# Logic_Engine_v0_1.net
KiCad netlist of a schematic drawn in EAGLE
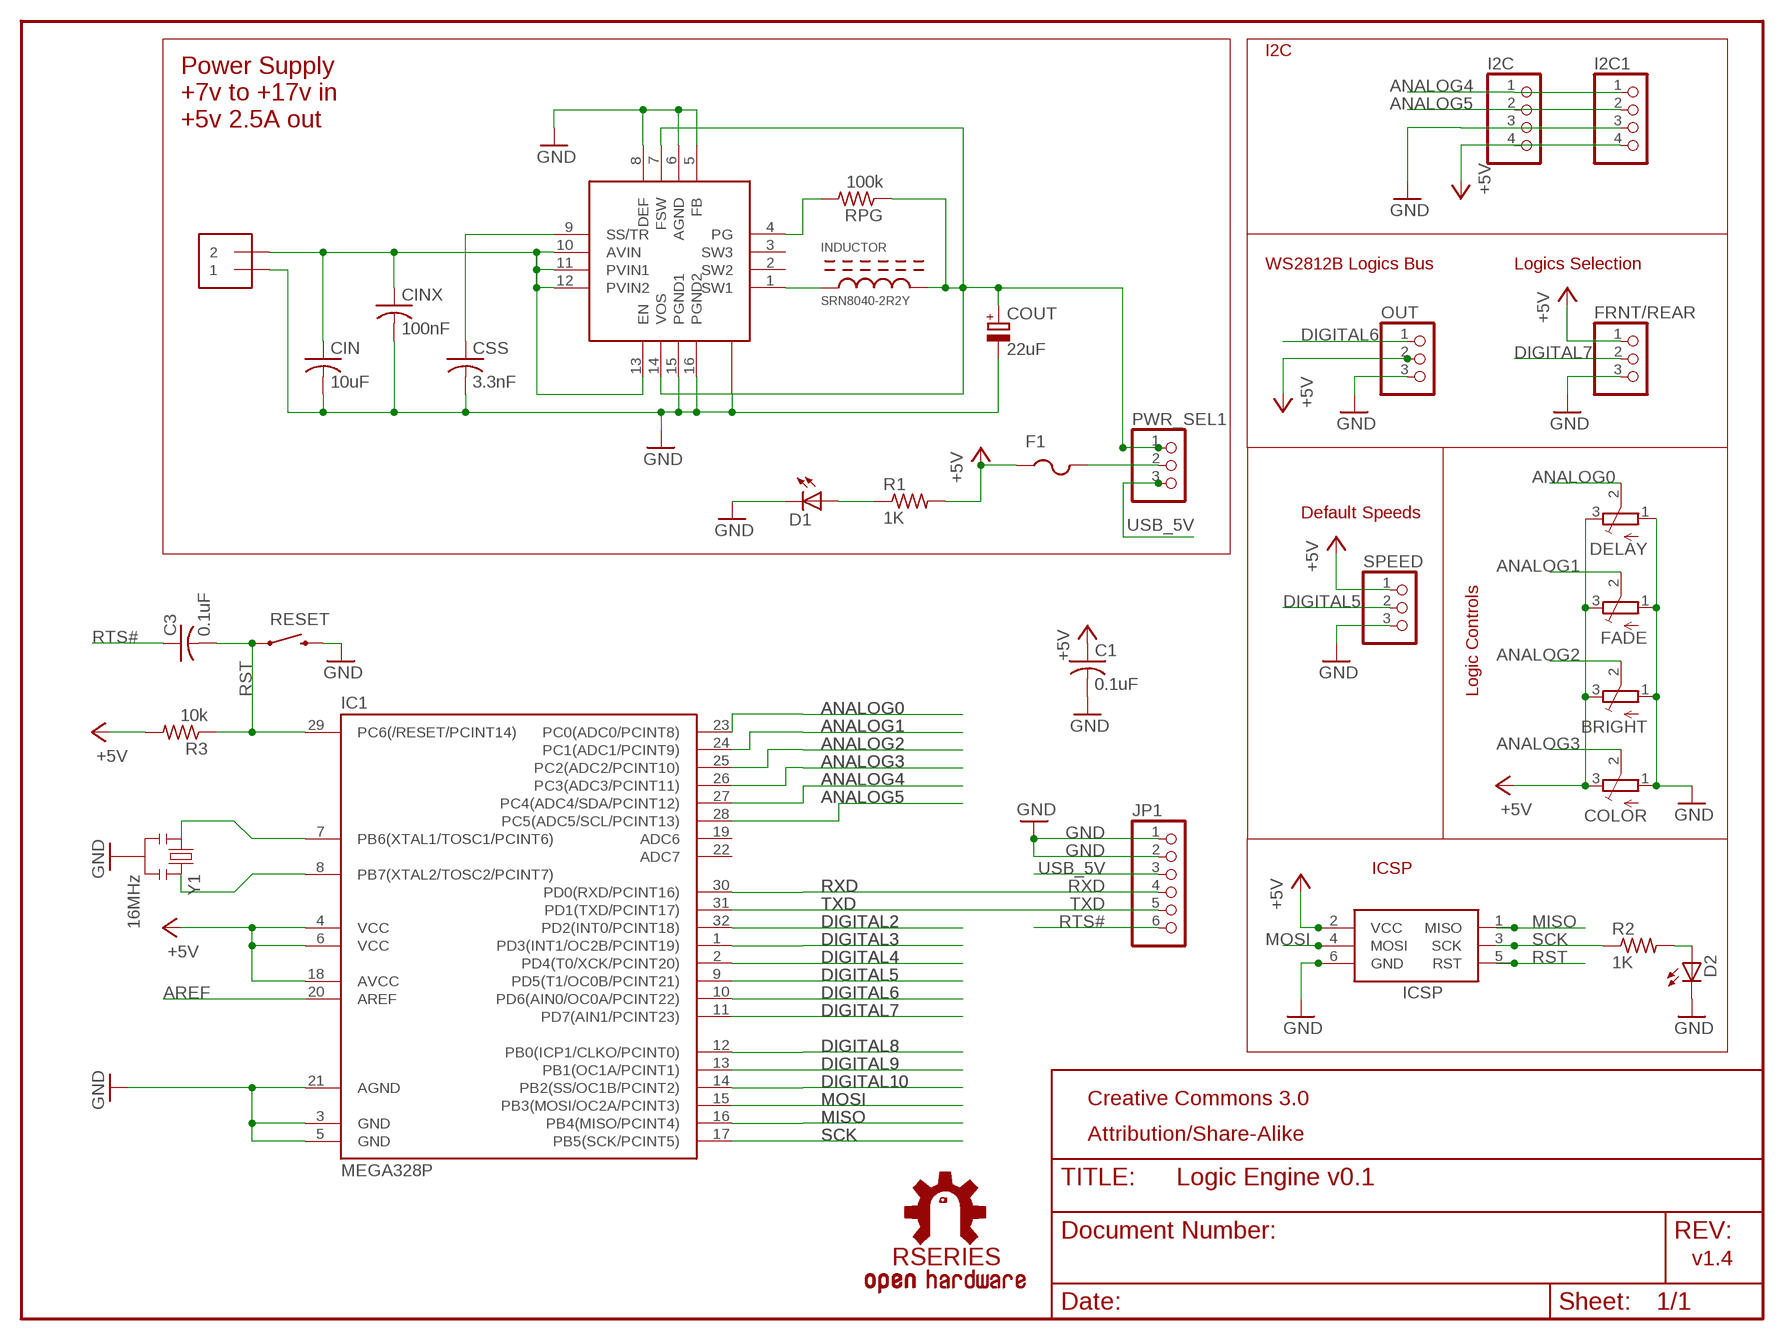
[diagram p0: schematic, sheet 1]

(export (version "E")
  (design (tool "Eeschema 10.0.6"))
  (components
    (comp (ref "BRIGHT")
      (value "TRIMPOT3364W")
      (footprint "eagle-import:3364")
      (libsource (lib "eagle-import") (part "TRIMPOT3364W"))
    )
    (comp (ref "C1")
      (value "0.1uF")
      (footprint "eagle-import:C0805K")
      (libsource (lib "eagle-import") (part "C-USC0805K"))
    )
    (comp (ref "C3")
      (value "0.1uF")
      (footprint "eagle-import:C0805K")
      (libsource (lib "eagle-import") (part "C-USC0805K"))
    )
    (comp (ref "CIN")
      (value "10uF")
      (footprint "eagle-import:C1206")
      (libsource (lib "eagle-import") (part "C-USC1206"))
    )
    (comp (ref "CINX")
      (value "100nF")
      (footprint "eagle-import:C0805K")
      (libsource (lib "eagle-import") (part "C-USC0805K"))
    )
    (comp (ref "COLOR")
      (value "TRIMPOT3364W")
      (footprint "eagle-import:3364")
      (libsource (lib "eagle-import") (part "TRIMPOT3364W"))
    )
    (comp (ref "COUT")
      (value "22uF")
      (footprint "eagle-import:CASE_B")
      (libsource (lib "eagle-import") (part "CAPACITOR_POL-CASE_B"))
    )
    (comp (ref "CSS")
      (value "3.3nF")
      (footprint "eagle-import:C0805K")
      (libsource (lib "eagle-import") (part "C-USC0805K"))
    )
    (comp (ref "D1")
      (value "LEDCHIPLED_1206")
      (footprint "eagle-import:CHIPLED_1206")
      (libsource (lib "eagle-import") (part "LEDCHIPLED_1206"))
    )
    (comp (ref "D2")
      (value "Green")
      (footprint "eagle-import:CHIPLED_1206")
      (libsource (lib "eagle-import") (part "LEDCHIPLED_1206"))
    )
    (comp (ref "DELAY")
      (value "TRIMPOT3364W")
      (footprint "eagle-import:3364")
      (libsource (lib "eagle-import") (part "TRIMPOT3364W"))
    )
    (comp (ref "EXT.PWR")
      (value "1X2-3.5MM")
      (footprint "eagle-import:1X2-3.5MM")
      (libsource (lib "eagle-import") (part "1X2-3.5MM"))
    )
    (comp (ref "F1")
      (value "PTCFUSE-1812")
      (footprint "eagle-import:1812")
      (libsource (lib "eagle-import") (part "PTCFUSE-1812"))
    )
    (comp (ref "FADE")
      (value "TRIMPOT3364W")
      (footprint "eagle-import:3364")
      (libsource (lib "eagle-import") (part "TRIMPOT3364W"))
    )
    (comp (ref "FRNT/REAR")
      (value "PINHD-1X3")
      (footprint "eagle-import:1X03")
      (libsource (lib "eagle-import") (part "PINHD-1X3"))
    )
    (comp (ref "I2C")
      (value "PINHD-1X4CB")
      (footprint "eagle-import:1X04-CB")
      (libsource (lib "eagle-import") (part "PINHD-1X4CB"))
    )
    (comp (ref "I2C1")
      (value "PINHD-1X4CB")
      (footprint "eagle-import:1X04-CB")
      (libsource (lib "eagle-import") (part "PINHD-1X4CB"))
    )
    (comp (ref "IC1")
      (value "MEGA328P")
      (footprint "eagle-import:TQFP32-08")
      (libsource (lib "eagle-import") (part "MEGA48/88/168-AU"))
    )
    (comp (ref "ICSP")
      (value "AVRISP-6")
      (footprint "eagle-import:AVRISP")
      (libsource (lib "eagle-import") (part "AVRISP-6"))
    )
    (comp (ref "INDUCTOR")
      (value "SRN8040-2R2Y")
      (footprint "eagle-import:SRN8040")
      (libsource (lib "eagle-import") (part "SRN8040"))
    )
    (comp (ref "JP1")
      (value "PINHD-1X6CLEAN")
      (footprint "eagle-import:1X06-CLEAN")
      (libsource (lib "eagle-import") (part "PINHD-1X6CLEAN"))
    )
    (comp (ref "OUT")
      (value "PINHD-1X3")
      (footprint "eagle-import:1X03")
      (libsource (lib "eagle-import") (part "PINHD-1X3"))
    )
    (comp (ref "PWR_SEL1")
      (value "PINHD-1X3")
      (footprint "eagle-import:1X03")
      (libsource (lib "eagle-import") (part "PINHD-1X3"))
    )
    (comp (ref "R1")
      (value "1K")
      (footprint "eagle-import:R0805")
      (libsource (lib "eagle-import") (part "R-US_R0805"))
    )
    (comp (ref "R2")
      (value "1K")
      (footprint "eagle-import:R0805")
      (libsource (lib "eagle-import") (part "R-US_R0805"))
    )
    (comp (ref "R3")
      (value "10k")
      (footprint "eagle-import:R0805")
      (libsource (lib "eagle-import") (part "R-US_R0805"))
    )
    (comp (ref "REG")
      (value "TPS62133")
      (footprint "eagle-import:TPS6213X")
      (libsource (lib "eagle-import") (part "TPS6213X"))
    )
    (comp (ref "RESET")
      (value "SWITCH-MOMENTARY-2SMD")
      (footprint "eagle-import:TACTILE_SWITCH_SMD")
      (libsource (lib "eagle-import") (part "SWITCH-MOMENTARY-2SMD"))
    )
    (comp (ref "RPG")
      (value "100k")
      (footprint "eagle-import:R0805")
      (libsource (lib "eagle-import") (part "R-US_R0805"))
    )
    (comp (ref "SPEED")
      (value "PINHD-1X3")
      (footprint "eagle-import:1X03")
      (libsource (lib "eagle-import") (part "PINHD-1X3"))
    )
    (comp (ref "U$2")
      (value "RSERIES-OSHW-LOGOMEDIUM")
      (footprint "eagle-import:RSERIES-OSHW-LOGO-MEDIUM")
      (libsource (lib "eagle-import") (part "RSERIES-OSHW-LOGOMEDIUM"))
    )
    (comp (ref "Y1")
      (value "16MHz")
      (footprint "eagle-import:RESONATOR-SMD")
      (libsource (lib "eagle-import") (part "RESONATOR16MHZ"))
    )
  )
  (nets
    (net (code "1") (name "+5V") (class "Default")
      (node (ref "BRIGHT") (pin "3") (pinfunction "E_3") (pintype "passive"))
      (node (ref "C1") (pin "1") (pinfunction "1_1") (pintype "passive"))
      (node (ref "COLOR") (pin "3") (pinfunction "E_3") (pintype "passive"))
      (node (ref "DELAY") (pin "3") (pinfunction "E_3") (pintype "passive"))
      (node (ref "F1") (pin "1") (pinfunction "1_1") (pintype "passive"))
      (node (ref "FADE") (pin "3") (pinfunction "E_3") (pintype "passive"))
      (node (ref "FRNT/REAR") (pin "1") (pinfunction "1_1") (pintype "passive"))
      (node (ref "I2C") (pin "4") (pinfunction "4_4") (pintype "passive"))
      (node (ref "I2C1") (pin "4") (pinfunction "4_4") (pintype "passive"))
      (node (ref "IC1") (pin "18") (pinfunction "AVCC_18") (pintype "passive"))
      (node (ref "IC1") (pin "4") (pinfunction "VCC_4") (pintype "power_in"))
      (node (ref "IC1") (pin "6") (pinfunction "VCC_6") (pintype "power_in"))
      (node (ref "ICSP") (pin "2") (pinfunction "VCC_2") (pintype "power_in"))
      (node (ref "OUT") (pin "2") (pinfunction "2_2") (pintype "passive"))
      (node (ref "R1") (pin "2") (pinfunction "2_2") (pintype "passive"))
      (node (ref "R3") (pin "2") (pinfunction "2_2") (pintype "passive"))
      (node (ref "SPEED") (pin "1") (pinfunction "1_1") (pintype "passive"))
    )
    (net (code "2") (name "/ANALOG0") (class "Default")
      (node (ref "DELAY") (pin "2") (pinfunction "S_2") (pintype "passive"))
      (node (ref "IC1") (pin "23") (pinfunction "PC0(ADC0/PCINT8)_23") (pintype "bidirectional"))
    )
    (net (code "3") (name "/ANALOG1") (class "Default")
      (node (ref "FADE") (pin "2") (pinfunction "S_2") (pintype "passive"))
      (node (ref "IC1") (pin "24") (pinfunction "PC1(ADC1/PCINT9)_24") (pintype "bidirectional"))
    )
    (net (code "4") (name "/ANALOG2") (class "Default")
      (node (ref "BRIGHT") (pin "2") (pinfunction "S_2") (pintype "passive"))
      (node (ref "IC1") (pin "25") (pinfunction "PC2(ADC2/PCINT10)_25") (pintype "bidirectional"))
    )
    (net (code "5") (name "/ANALOG3") (class "Default")
      (node (ref "COLOR") (pin "2") (pinfunction "S_2") (pintype "passive"))
      (node (ref "IC1") (pin "26") (pinfunction "PC3(ADC3/PCINT11)_26") (pintype "bidirectional"))
    )
    (net (code "6") (name "/ANALOG4") (class "Default")
      (node (ref "I2C") (pin "1") (pinfunction "1_1") (pintype "passive"))
      (node (ref "I2C1") (pin "1") (pinfunction "1_1") (pintype "passive"))
      (node (ref "IC1") (pin "27") (pinfunction "PC4(ADC4/SDA/PCINT12)_27") (pintype "bidirectional"))
    )
    (net (code "7") (name "/ANALOG5") (class "Default")
      (node (ref "I2C") (pin "2") (pinfunction "2_2") (pintype "passive"))
      (node (ref "I2C1") (pin "2") (pinfunction "2_2") (pintype "passive"))
      (node (ref "IC1") (pin "28") (pinfunction "PC5(ADC5/SCL/PCINT13)_28") (pintype "bidirectional"))
    )
    (net (code "8") (name "/AREF") (class "Default")
      (node (ref "IC1") (pin "20") (pinfunction "AREF_20") (pintype "passive"))
    )
    (net (code "9") (name "/DIGITAL2") (class "Default")
      (node (ref "IC1") (pin "32") (pinfunction "PD2(INT0/PCINT18)_32") (pintype "bidirectional"))
    )
    (net (code "10") (name "/DIGITAL3") (class "Default")
      (node (ref "IC1") (pin "1") (pinfunction "PD3(INT1/OC2B/PCINT19)_1") (pintype "bidirectional"))
    )
    (net (code "11") (name "/DIGITAL4") (class "Default")
      (node (ref "IC1") (pin "2") (pinfunction "PD4(T0/XCK/PCINT20)_2") (pintype "bidirectional"))
    )
    (net (code "12") (name "/DIGITAL5") (class "Default")
      (node (ref "IC1") (pin "9") (pinfunction "PD5(T1/OC0B/PCINT21)_9") (pintype "bidirectional"))
      (node (ref "SPEED") (pin "2") (pinfunction "2_2") (pintype "passive"))
    )
    (net (code "13") (name "/DIGITAL6") (class "Default")
      (node (ref "IC1") (pin "10") (pinfunction "PD6(AIN0/OC0A/PCINT22)_10") (pintype "bidirectional"))
      (node (ref "OUT") (pin "1") (pinfunction "1_1") (pintype "passive"))
    )
    (net (code "14") (name "/DIGITAL7") (class "Default")
      (node (ref "FRNT/REAR") (pin "2") (pinfunction "2_2") (pintype "passive"))
      (node (ref "IC1") (pin "11") (pinfunction "PD7(AIN1/PCINT23)_11") (pintype "bidirectional"))
    )
    (net (code "15") (name "/DIGITAL8") (class "Default")
      (node (ref "IC1") (pin "12") (pinfunction "PB0(ICP1/CLKO/PCINT0)_12") (pintype "bidirectional"))
    )
    (net (code "16") (name "/DIGITAL9") (class "Default")
      (node (ref "IC1") (pin "13") (pinfunction "PB1(OC1A/PCINT1)_13") (pintype "bidirectional"))
    )
    (net (code "17") (name "/DIGITAL10") (class "Default")
      (node (ref "IC1") (pin "14") (pinfunction "PB2(SS/OC1B/PCINT2)_14") (pintype "bidirectional"))
    )
    (net (code "18") (name "/MISO") (class "Default")
      (node (ref "IC1") (pin "16") (pinfunction "PB4(MISO/PCINT4)_16") (pintype "bidirectional"))
      (node (ref "ICSP") (pin "1") (pinfunction "MISO_1") (pintype "input"))
    )
    (net (code "19") (name "/MOSI") (class "Default")
      (node (ref "IC1") (pin "15") (pinfunction "PB3(MOSI/OC2A/PCINT3)_15") (pintype "bidirectional"))
      (node (ref "ICSP") (pin "4") (pinfunction "MOSI_4") (pintype "output"))
    )
    (net (code "20") (name "/RST") (class "Default")
      (node (ref "C3") (pin "2") (pinfunction "2_2") (pintype "passive"))
      (node (ref "IC1") (pin "29") (pinfunction "PC6(/RESET/PCINT14)_29") (pintype "bidirectional"))
      (node (ref "ICSP") (pin "5") (pinfunction "RST_5") (pintype "output"))
      (node (ref "R3") (pin "1") (pinfunction "1_1") (pintype "passive"))
      (node (ref "RESET") (pin "1") (pinfunction "1_1") (pintype "passive"))
    )
    (net (code "21") (name "/RTS#") (class "Default")
      (node (ref "C3") (pin "1") (pinfunction "1_1") (pintype "passive"))
      (node (ref "JP1") (pin "6") (pinfunction "6_6") (pintype "passive"))
    )
    (net (code "22") (name "/RXD") (class "Default")
      (node (ref "IC1") (pin "30") (pinfunction "PD0(RXD/PCINT16)_30") (pintype "bidirectional"))
      (node (ref "JP1") (pin "4") (pinfunction "4_4") (pintype "passive"))
    )
    (net (code "23") (name "/SCK") (class "Default")
      (node (ref "IC1") (pin "17") (pinfunction "PB5(SCK/PCINT5)_17") (pintype "bidirectional"))
      (node (ref "ICSP") (pin "3") (pinfunction "SCK_3") (pintype "output"))
      (node (ref "R2") (pin "1") (pinfunction "1_1") (pintype "passive"))
    )
    (net (code "24") (name "/TXD") (class "Default")
      (node (ref "IC1") (pin "31") (pinfunction "PD1(TXD/PCINT17)_31") (pintype "bidirectional"))
      (node (ref "JP1") (pin "5") (pinfunction "5_5") (pintype "passive"))
    )
    (net (code "25") (name "/USB_5V") (class "Default")
      (node (ref "JP1") (pin "3") (pinfunction "3_3") (pintype "passive"))
      (node (ref "PWR_SEL1") (pin "3") (pinfunction "3_3") (pintype "passive"))
    )
    (net (code "26") (name "GND") (class "Default")
      (node (ref "BRIGHT") (pin "1") (pinfunction "A_1") (pintype "passive"))
      (node (ref "C1") (pin "2") (pinfunction "2_2") (pintype "passive"))
      (node (ref "CIN") (pin "2") (pinfunction "2_2") (pintype "passive"))
      (node (ref "CINX") (pin "2") (pinfunction "2_2") (pintype "passive"))
      (node (ref "COLOR") (pin "1") (pinfunction "A_1") (pintype "passive"))
      (node (ref "COUT") (pin "-") (pinfunction "-_-") (pintype "passive"))
      (node (ref "CSS") (pin "2") (pinfunction "2_2") (pintype "passive"))
      (node (ref "D1") (pin "C") (pinfunction "C_C") (pintype "passive"))
      (node (ref "D2") (pin "C") (pinfunction "C_C") (pintype "passive"))
      (node (ref "DELAY") (pin "1") (pinfunction "A_1") (pintype "passive"))
      (node (ref "EXT.PWR") (pin "1") (pinfunction "1_1") (pintype "passive"))
      (node (ref "FADE") (pin "1") (pinfunction "A_1") (pintype "passive"))
      (node (ref "FRNT/REAR") (pin "3") (pinfunction "3_3") (pintype "passive"))
      (node (ref "I2C") (pin "3") (pinfunction "3_3") (pintype "passive"))
      (node (ref "I2C1") (pin "3") (pinfunction "3_3") (pintype "passive"))
      (node (ref "IC1") (pin "21") (pinfunction "AGND_21") (pintype "power_in"))
      (node (ref "IC1") (pin "3") (pinfunction "GND_3") (pintype "power_in"))
      (node (ref "IC1") (pin "5") (pinfunction "GND_5") (pintype "power_in"))
      (node (ref "ICSP") (pin "6") (pinfunction "GND_6") (pintype "power_in"))
      (node (ref "JP1") (pin "1") (pinfunction "1_1") (pintype "passive"))
      (node (ref "JP1") (pin "2") (pinfunction "2_2") (pintype "passive"))
      (node (ref "OUT") (pin "3") (pinfunction "3_3") (pintype "passive"))
      (node (ref "REG") (pin "15") (pinfunction "PGND1_15") (pintype "bidirectional"))
      (node (ref "REG") (pin "16") (pinfunction "PGND2_16") (pintype "bidirectional"))
      (node (ref "REG") (pin "17-THERMALPAD") (pinfunction "THERM_17-THERMALPAD") (pintype "bidirectional"))
      (node (ref "REG") (pin "5") (pinfunction "FB_5") (pintype "bidirectional"))
      (node (ref "REG") (pin "6") (pinfunction "AGND_6") (pintype "bidirectional"))
      (node (ref "REG") (pin "8") (pinfunction "DEF_8") (pintype "bidirectional"))
      (node (ref "RESET") (pin "3") (pinfunction "2_3") (pintype "passive"))
      (node (ref "SPEED") (pin "3") (pinfunction "3_3") (pintype "passive"))
      (node (ref "Y1") (pin "2") (pinfunction "2_2") (pintype "passive"))
    )
    (net (code "27") (name "Net-(D1-PadA)") (class "Default")
      (node (ref "D1") (pin "A") (pinfunction "A_A") (pintype "passive"))
      (node (ref "R1") (pin "1") (pinfunction "1_1") (pintype "passive"))
    )
    (net (code "28") (name "Net-(D2-PadA)") (class "Default")
      (node (ref "D2") (pin "A") (pinfunction "A_A") (pintype "passive"))
      (node (ref "R2") (pin "2") (pinfunction "2_2") (pintype "passive"))
    )
    (net (code "29") (name "Net-(F1-Pad2)") (class "Default")
      (node (ref "F1") (pin "2") (pinfunction "2_2") (pintype "passive"))
      (node (ref "PWR_SEL1") (pin "2") (pinfunction "2_2") (pintype "passive"))
    )
    (net (code "30") (name "Net-(IC1-PB6(XTAL1{slash}TOSC1{slash}PCINT6))") (class "Default")
      (node (ref "IC1") (pin "7") (pinfunction "PB6(XTAL1/TOSC1/PCINT6)_7") (pintype "bidirectional"))
      (node (ref "Y1") (pin "1") (pinfunction "1_1") (pintype "passive"))
    )
    (net (code "31") (name "Net-(IC1-PB7(XTAL2{slash}TOSC2{slash}PCINT7))") (class "Default")
      (node (ref "IC1") (pin "8") (pinfunction "PB7(XTAL2/TOSC2/PCINT7)_8") (pintype "bidirectional"))
      (node (ref "Y1") (pin "3") (pinfunction "3_3") (pintype "passive"))
    )
    (net (code "32") (name "Net-(INDUCTOR-P1)") (class "Default")
      (node (ref "INDUCTOR") (pin "P$1") (pinfunction "P1_P$1") (pintype "bidirectional"))
      (node (ref "REG") (pin "1") (pinfunction "SW1_1") (pintype "bidirectional"))
    )
    (net (code "33") (name "Net-(INDUCTOR-P2)") (class "Default")
      (node (ref "COUT") (pin "+") (pinfunction "+_+") (pintype "passive"))
      (node (ref "INDUCTOR") (pin "P$2") (pinfunction "P2_P$2") (pintype "bidirectional"))
      (node (ref "PWR_SEL1") (pin "1") (pinfunction "1_1") (pintype "passive"))
      (node (ref "REG") (pin "14") (pinfunction "VOS_14") (pintype "bidirectional"))
      (node (ref "REG") (pin "7") (pinfunction "FSW_7") (pintype "bidirectional"))
      (node (ref "RPG") (pin "1") (pinfunction "1_1") (pintype "passive"))
    )
    (net (code "34") (name "Net-(REG-AVIN)") (class "Default")
      (node (ref "CIN") (pin "1") (pinfunction "1_1") (pintype "passive"))
      (node (ref "CINX") (pin "1") (pinfunction "1_1") (pintype "passive"))
      (node (ref "EXT.PWR") (pin "2") (pinfunction "2_2") (pintype "passive"))
      (node (ref "REG") (pin "10") (pinfunction "AVIN_10") (pintype "bidirectional"))
      (node (ref "REG") (pin "11") (pinfunction "PVIN1_11") (pintype "bidirectional"))
      (node (ref "REG") (pin "12") (pinfunction "PVIN2_12") (pintype "bidirectional"))
      (node (ref "REG") (pin "13") (pinfunction "EN_13") (pintype "bidirectional"))
    )
    (net (code "35") (name "Net-(REG-PG)") (class "Default")
      (node (ref "REG") (pin "4") (pinfunction "PG_4") (pintype "bidirectional"))
      (node (ref "RPG") (pin "2") (pinfunction "2_2") (pintype "passive"))
    )
    (net (code "36") (name "Net-(REG-SS{slash}TR)") (class "Default")
      (node (ref "CSS") (pin "1") (pinfunction "1_1") (pintype "passive"))
      (node (ref "REG") (pin "9") (pinfunction "SS/TR_9") (pintype "bidirectional"))
    )
    (net (code "37") (name "unconnected-(IC1-ADC6-Pad19)") (class "Default")
      (node (ref "IC1") (pin "19") (pinfunction "ADC6_19") (pintype "passive"))
    )
    (net (code "38") (name "unconnected-(IC1-ADC7-Pad22)") (class "Default")
      (node (ref "IC1") (pin "22") (pinfunction "ADC7_22") (pintype "passive"))
    )
    (net (code "39") (name "unconnected-(REG-SW2-Pad2)") (class "Default")
      (node (ref "REG") (pin "2") (pinfunction "SW2_2") (pintype "bidirectional"))
    )
    (net (code "40") (name "unconnected-(REG-SW3-Pad3)") (class "Default")
      (node (ref "REG") (pin "3") (pinfunction "SW3_3") (pintype "bidirectional"))
    )
  )
)
